# h.net
KiCad netlist of a schematic drawn in EAGLE
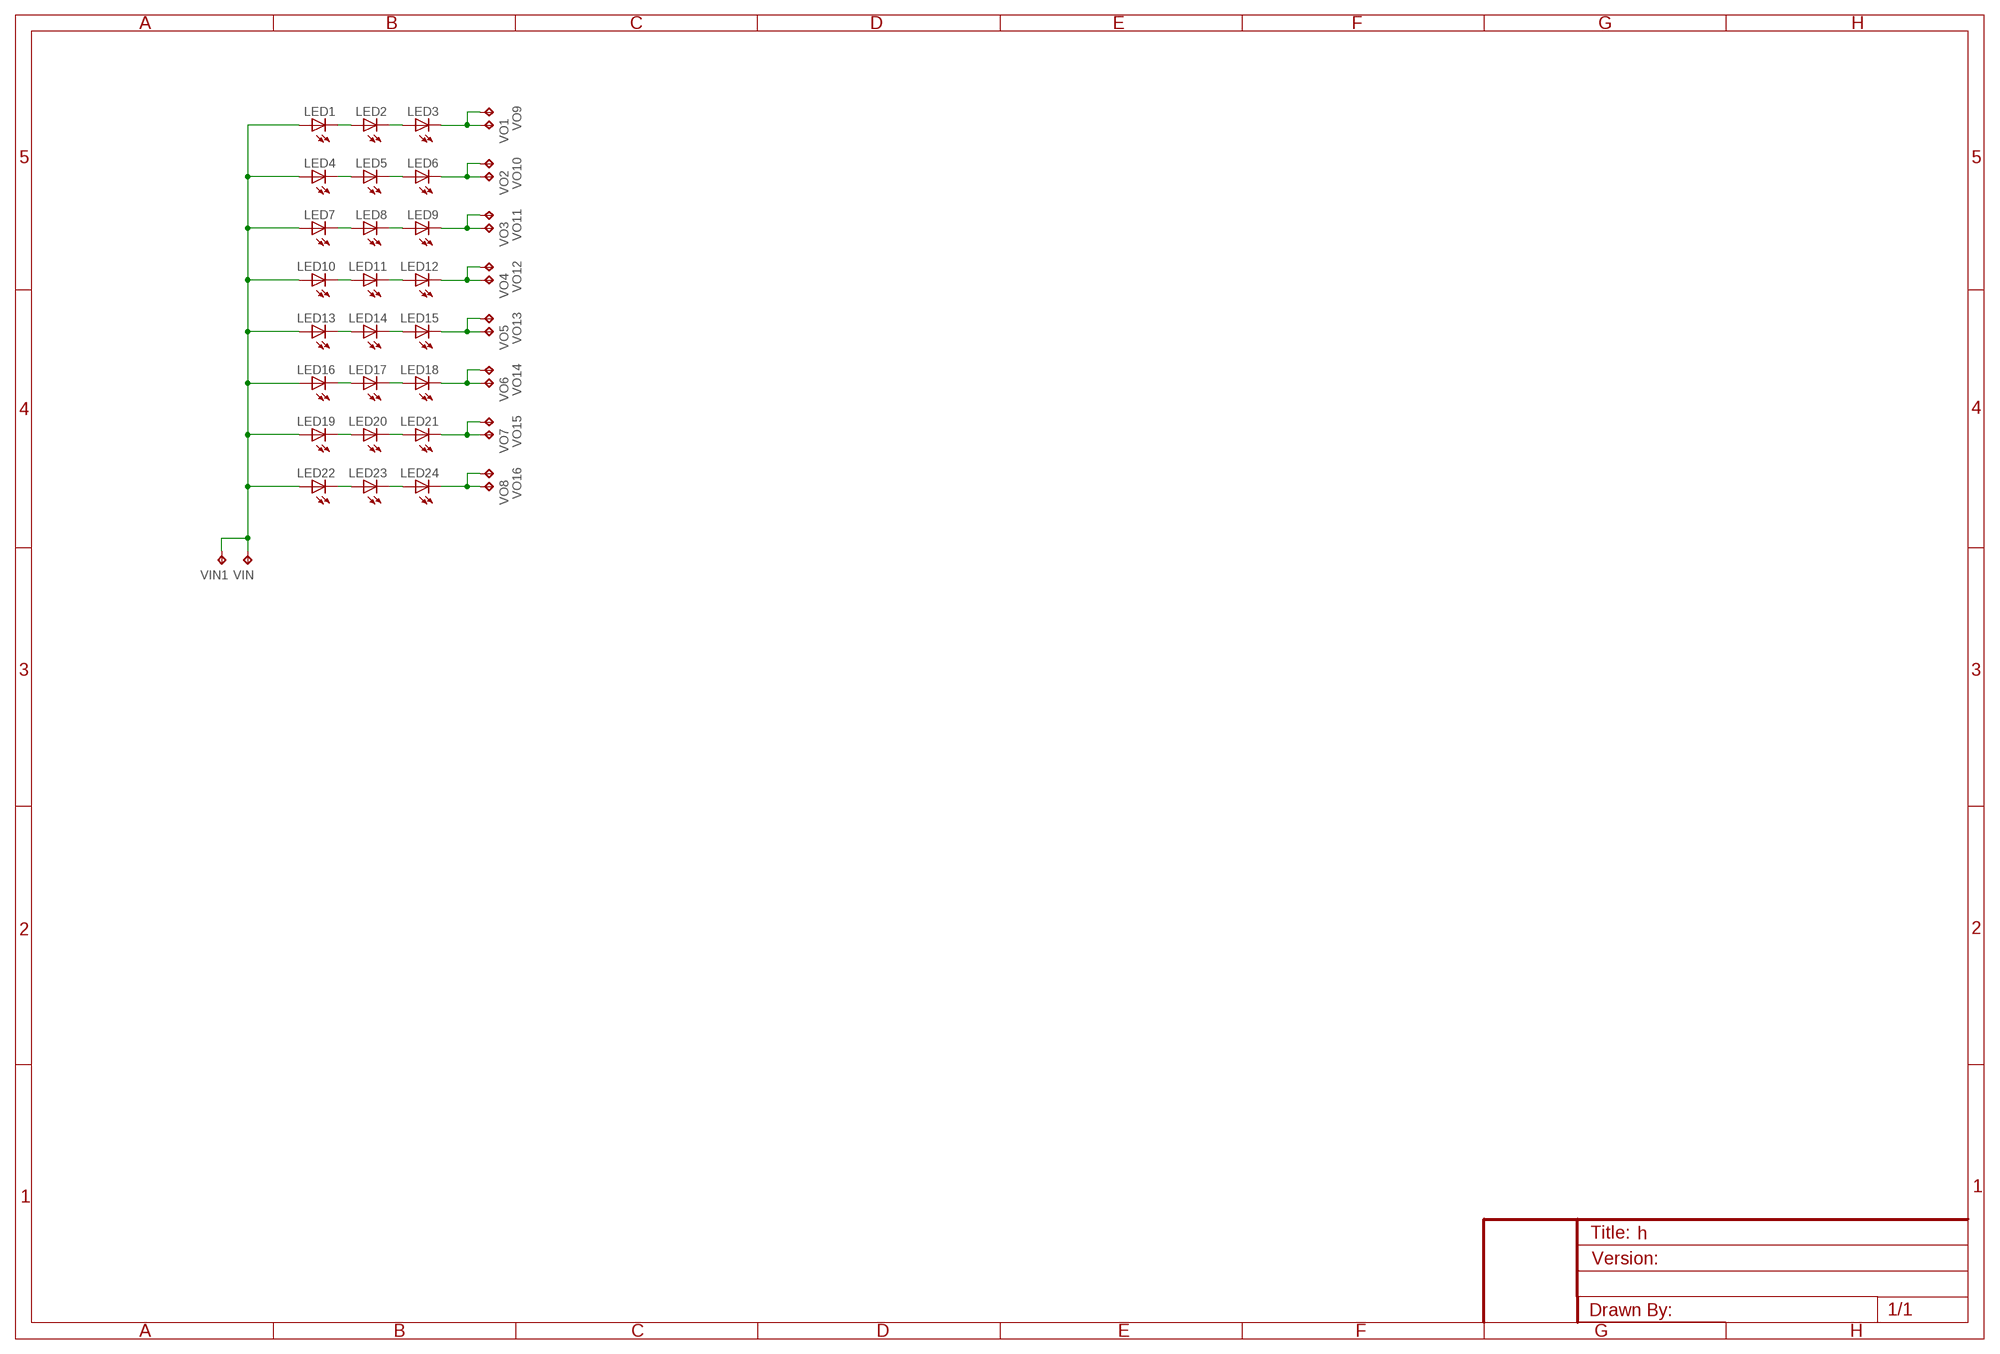
[diagram p0: schematic, sheet 1]

(export (version "E")
  (design (tool "Eeschema 10.0.6"))
  (components
    (comp (ref "LED1")
      (value "LED0805")
      (footprint "eagle-import:LED_0805")
      (libsource (lib "eagle-import") (part "LED0805"))
    )
    (comp (ref "LED2")
      (value "LED0805")
      (footprint "eagle-import:LED_0805")
      (libsource (lib "eagle-import") (part "LED0805"))
    )
    (comp (ref "LED3")
      (value "LED0805")
      (footprint "eagle-import:LED_0805")
      (libsource (lib "eagle-import") (part "LED0805"))
    )
    (comp (ref "LED4")
      (value "LED0805")
      (footprint "eagle-import:LED_0805")
      (libsource (lib "eagle-import") (part "LED0805"))
    )
    (comp (ref "LED5")
      (value "LED0805")
      (footprint "eagle-import:LED_0805")
      (libsource (lib "eagle-import") (part "LED0805"))
    )
    (comp (ref "LED6")
      (value "LED0805")
      (footprint "eagle-import:LED_0805")
      (libsource (lib "eagle-import") (part "LED0805"))
    )
    (comp (ref "LED7")
      (value "LED0805")
      (footprint "eagle-import:LED_0805")
      (libsource (lib "eagle-import") (part "LED0805"))
    )
    (comp (ref "LED8")
      (value "LED0805")
      (footprint "eagle-import:LED_0805")
      (libsource (lib "eagle-import") (part "LED0805"))
    )
    (comp (ref "LED9")
      (value "LED0805")
      (footprint "eagle-import:LED_0805")
      (libsource (lib "eagle-import") (part "LED0805"))
    )
    (comp (ref "LED10")
      (value "LED0805")
      (footprint "eagle-import:LED_0805")
      (libsource (lib "eagle-import") (part "LED0805"))
    )
    (comp (ref "LED11")
      (value "LED0805")
      (footprint "eagle-import:LED_0805")
      (libsource (lib "eagle-import") (part "LED0805"))
    )
    (comp (ref "LED12")
      (value "LED0805")
      (footprint "eagle-import:LED_0805")
      (libsource (lib "eagle-import") (part "LED0805"))
    )
    (comp (ref "LED13")
      (value "LED0805")
      (footprint "eagle-import:LED_0805")
      (libsource (lib "eagle-import") (part "LED0805"))
    )
    (comp (ref "LED14")
      (value "LED0805")
      (footprint "eagle-import:LED_0805")
      (libsource (lib "eagle-import") (part "LED0805"))
    )
    (comp (ref "LED15")
      (value "LED0805")
      (footprint "eagle-import:LED_0805")
      (libsource (lib "eagle-import") (part "LED0805"))
    )
    (comp (ref "LED16")
      (value "LED0805")
      (footprint "eagle-import:LED_0805")
      (libsource (lib "eagle-import") (part "LED0805"))
    )
    (comp (ref "LED17")
      (value "LED0805")
      (footprint "eagle-import:LED_0805")
      (libsource (lib "eagle-import") (part "LED0805"))
    )
    (comp (ref "LED18")
      (value "LED0805")
      (footprint "eagle-import:LED_0805")
      (libsource (lib "eagle-import") (part "LED0805"))
    )
    (comp (ref "LED19")
      (value "LED0805")
      (footprint "eagle-import:LED_0805")
      (libsource (lib "eagle-import") (part "LED0805"))
    )
    (comp (ref "LED20")
      (value "LED0805")
      (footprint "eagle-import:LED_0805")
      (libsource (lib "eagle-import") (part "LED0805"))
    )
    (comp (ref "LED21")
      (value "LED0805")
      (footprint "eagle-import:LED_0805")
      (libsource (lib "eagle-import") (part "LED0805"))
    )
    (comp (ref "LED22")
      (value "LED0805")
      (footprint "eagle-import:LED_0805")
      (libsource (lib "eagle-import") (part "LED0805"))
    )
    (comp (ref "LED23")
      (value "LED0805")
      (footprint "eagle-import:LED_0805")
      (libsource (lib "eagle-import") (part "LED0805"))
    )
    (comp (ref "LED24")
      (value "LED0805")
      (footprint "eagle-import:LED_0805")
      (libsource (lib "eagle-import") (part "LED0805"))
    )
    (comp (ref "VIN")
      (value "TEST_POINTPAD1-20")
      (footprint "eagle-import:P1-20")
      (libsource (lib "eagle-import") (part "TEST_POINTPAD1-20"))
    )
    (comp (ref "VIN1")
      (value "TEST_POINTPAD1-20")
      (footprint "eagle-import:P1-20")
      (libsource (lib "eagle-import") (part "TEST_POINTPAD1-20"))
    )
    (comp (ref "VO1")
      (value "TEST_POINTPAD1-20")
      (footprint "eagle-import:P1-20")
      (libsource (lib "eagle-import") (part "TEST_POINTPAD1-20"))
    )
    (comp (ref "VO2")
      (value "TEST_POINTPAD1-20")
      (footprint "eagle-import:P1-20")
      (libsource (lib "eagle-import") (part "TEST_POINTPAD1-20"))
    )
    (comp (ref "VO3")
      (value "TEST_POINTPAD1-20")
      (footprint "eagle-import:P1-20")
      (libsource (lib "eagle-import") (part "TEST_POINTPAD1-20"))
    )
    (comp (ref "VO4")
      (value "TEST_POINTPAD1-20")
      (footprint "eagle-import:P1-20")
      (libsource (lib "eagle-import") (part "TEST_POINTPAD1-20"))
    )
    (comp (ref "VO5")
      (value "TEST_POINTPAD1-20")
      (footprint "eagle-import:P1-20")
      (libsource (lib "eagle-import") (part "TEST_POINTPAD1-20"))
    )
    (comp (ref "VO6")
      (value "TEST_POINTPAD1-20")
      (footprint "eagle-import:P1-20")
      (libsource (lib "eagle-import") (part "TEST_POINTPAD1-20"))
    )
    (comp (ref "VO7")
      (value "TEST_POINTPAD1-20")
      (footprint "eagle-import:P1-20")
      (libsource (lib "eagle-import") (part "TEST_POINTPAD1-20"))
    )
    (comp (ref "VO8")
      (value "TEST_POINTPAD1-20")
      (footprint "eagle-import:P1-20")
      (libsource (lib "eagle-import") (part "TEST_POINTPAD1-20"))
    )
    (comp (ref "VO9")
      (value "TEST_POINTPAD1-20")
      (footprint "eagle-import:P1-20")
      (libsource (lib "eagle-import") (part "TEST_POINTPAD1-20"))
    )
    (comp (ref "VO10")
      (value "TEST_POINTPAD1-20")
      (footprint "eagle-import:P1-20")
      (libsource (lib "eagle-import") (part "TEST_POINTPAD1-20"))
    )
    (comp (ref "VO11")
      (value "TEST_POINTPAD1-20")
      (footprint "eagle-import:P1-20")
      (libsource (lib "eagle-import") (part "TEST_POINTPAD1-20"))
    )
    (comp (ref "VO12")
      (value "TEST_POINTPAD1-20")
      (footprint "eagle-import:P1-20")
      (libsource (lib "eagle-import") (part "TEST_POINTPAD1-20"))
    )
    (comp (ref "VO13")
      (value "TEST_POINTPAD1-20")
      (footprint "eagle-import:P1-20")
      (libsource (lib "eagle-import") (part "TEST_POINTPAD1-20"))
    )
    (comp (ref "VO14")
      (value "TEST_POINTPAD1-20")
      (footprint "eagle-import:P1-20")
      (libsource (lib "eagle-import") (part "TEST_POINTPAD1-20"))
    )
    (comp (ref "VO15")
      (value "TEST_POINTPAD1-20")
      (footprint "eagle-import:P1-20")
      (libsource (lib "eagle-import") (part "TEST_POINTPAD1-20"))
    )
    (comp (ref "VO16")
      (value "TEST_POINTPAD1-20")
      (footprint "eagle-import:P1-20")
      (libsource (lib "eagle-import") (part "TEST_POINTPAD1-20"))
    )
  )
  (nets
    (net (code "1") (name "Net-(LED1-PadA)") (class "Default")
      (node (ref "LED1") (pin "A") (pinfunction "A_A") (pintype "passive"))
      (node (ref "LED10") (pin "A") (pinfunction "A_A") (pintype "passive"))
      (node (ref "LED13") (pin "A") (pinfunction "A_A") (pintype "passive"))
      (node (ref "LED16") (pin "A") (pinfunction "A_A") (pintype "passive"))
      (node (ref "LED19") (pin "A") (pinfunction "A_A") (pintype "passive"))
      (node (ref "LED22") (pin "A") (pinfunction "A_A") (pintype "passive"))
      (node (ref "LED4") (pin "A") (pinfunction "A_A") (pintype "passive"))
      (node (ref "LED7") (pin "A") (pinfunction "A_A") (pintype "passive"))
      (node (ref "VIN") (pin "TP") (pinfunction "TP_TP") (pintype "input"))
      (node (ref "VIN1") (pin "TP") (pinfunction "TP_TP") (pintype "input"))
    )
    (net (code "2") (name "Net-(LED1-PadC)") (class "Default")
      (node (ref "LED1") (pin "C") (pinfunction "C_C") (pintype "passive"))
      (node (ref "LED2") (pin "A") (pinfunction "A_A") (pintype "passive"))
    )
    (net (code "3") (name "Net-(LED2-PadC)") (class "Default")
      (node (ref "LED2") (pin "C") (pinfunction "C_C") (pintype "passive"))
      (node (ref "LED3") (pin "A") (pinfunction "A_A") (pintype "passive"))
    )
    (net (code "4") (name "Net-(LED3-PadC)") (class "Default")
      (node (ref "LED3") (pin "C") (pinfunction "C_C") (pintype "passive"))
      (node (ref "VO1") (pin "TP") (pinfunction "TP_TP") (pintype "input"))
      (node (ref "VO9") (pin "TP") (pinfunction "TP_TP") (pintype "input"))
    )
    (net (code "5") (name "Net-(LED4-PadC)") (class "Default")
      (node (ref "LED4") (pin "C") (pinfunction "C_C") (pintype "passive"))
      (node (ref "LED5") (pin "A") (pinfunction "A_A") (pintype "passive"))
    )
    (net (code "6") (name "Net-(LED5-PadC)") (class "Default")
      (node (ref "LED5") (pin "C") (pinfunction "C_C") (pintype "passive"))
      (node (ref "LED6") (pin "A") (pinfunction "A_A") (pintype "passive"))
    )
    (net (code "7") (name "Net-(LED6-PadC)") (class "Default")
      (node (ref "LED6") (pin "C") (pinfunction "C_C") (pintype "passive"))
      (node (ref "VO10") (pin "TP") (pinfunction "TP_TP") (pintype "input"))
      (node (ref "VO2") (pin "TP") (pinfunction "TP_TP") (pintype "input"))
    )
    (net (code "8") (name "Net-(LED7-PadC)") (class "Default")
      (node (ref "LED7") (pin "C") (pinfunction "C_C") (pintype "passive"))
      (node (ref "LED8") (pin "A") (pinfunction "A_A") (pintype "passive"))
    )
    (net (code "9") (name "Net-(LED8-PadC)") (class "Default")
      (node (ref "LED8") (pin "C") (pinfunction "C_C") (pintype "passive"))
      (node (ref "LED9") (pin "A") (pinfunction "A_A") (pintype "passive"))
    )
    (net (code "10") (name "Net-(LED9-PadC)") (class "Default")
      (node (ref "LED9") (pin "C") (pinfunction "C_C") (pintype "passive"))
      (node (ref "VO11") (pin "TP") (pinfunction "TP_TP") (pintype "input"))
      (node (ref "VO3") (pin "TP") (pinfunction "TP_TP") (pintype "input"))
    )
    (net (code "11") (name "Net-(LED10-PadC)") (class "Default")
      (node (ref "LED10") (pin "C") (pinfunction "C_C") (pintype "passive"))
      (node (ref "LED11") (pin "A") (pinfunction "A_A") (pintype "passive"))
    )
    (net (code "12") (name "Net-(LED11-PadC)") (class "Default")
      (node (ref "LED11") (pin "C") (pinfunction "C_C") (pintype "passive"))
      (node (ref "LED12") (pin "A") (pinfunction "A_A") (pintype "passive"))
    )
    (net (code "13") (name "Net-(LED12-PadC)") (class "Default")
      (node (ref "LED12") (pin "C") (pinfunction "C_C") (pintype "passive"))
      (node (ref "VO12") (pin "TP") (pinfunction "TP_TP") (pintype "input"))
      (node (ref "VO4") (pin "TP") (pinfunction "TP_TP") (pintype "input"))
    )
    (net (code "14") (name "Net-(LED13-PadC)") (class "Default")
      (node (ref "LED13") (pin "C") (pinfunction "C_C") (pintype "passive"))
      (node (ref "LED14") (pin "A") (pinfunction "A_A") (pintype "passive"))
    )
    (net (code "15") (name "Net-(LED14-PadC)") (class "Default")
      (node (ref "LED14") (pin "C") (pinfunction "C_C") (pintype "passive"))
      (node (ref "LED15") (pin "A") (pinfunction "A_A") (pintype "passive"))
    )
    (net (code "16") (name "Net-(LED15-PadC)") (class "Default")
      (node (ref "LED15") (pin "C") (pinfunction "C_C") (pintype "passive"))
      (node (ref "VO13") (pin "TP") (pinfunction "TP_TP") (pintype "input"))
      (node (ref "VO5") (pin "TP") (pinfunction "TP_TP") (pintype "input"))
    )
    (net (code "17") (name "Net-(LED16-PadC)") (class "Default")
      (node (ref "LED16") (pin "C") (pinfunction "C_C") (pintype "passive"))
      (node (ref "LED17") (pin "A") (pinfunction "A_A") (pintype "passive"))
    )
    (net (code "18") (name "Net-(LED17-PadC)") (class "Default")
      (node (ref "LED17") (pin "C") (pinfunction "C_C") (pintype "passive"))
      (node (ref "LED18") (pin "A") (pinfunction "A_A") (pintype "passive"))
    )
    (net (code "19") (name "Net-(LED18-PadC)") (class "Default")
      (node (ref "LED18") (pin "C") (pinfunction "C_C") (pintype "passive"))
      (node (ref "VO14") (pin "TP") (pinfunction "TP_TP") (pintype "input"))
      (node (ref "VO6") (pin "TP") (pinfunction "TP_TP") (pintype "input"))
    )
    (net (code "20") (name "Net-(LED19-PadC)") (class "Default")
      (node (ref "LED19") (pin "C") (pinfunction "C_C") (pintype "passive"))
      (node (ref "LED20") (pin "A") (pinfunction "A_A") (pintype "passive"))
    )
    (net (code "21") (name "Net-(LED20-PadC)") (class "Default")
      (node (ref "LED20") (pin "C") (pinfunction "C_C") (pintype "passive"))
      (node (ref "LED21") (pin "A") (pinfunction "A_A") (pintype "passive"))
    )
    (net (code "22") (name "Net-(LED21-PadC)") (class "Default")
      (node (ref "LED21") (pin "C") (pinfunction "C_C") (pintype "passive"))
      (node (ref "VO15") (pin "TP") (pinfunction "TP_TP") (pintype "input"))
      (node (ref "VO7") (pin "TP") (pinfunction "TP_TP") (pintype "input"))
    )
    (net (code "23") (name "Net-(LED22-PadC)") (class "Default")
      (node (ref "LED22") (pin "C") (pinfunction "C_C") (pintype "passive"))
      (node (ref "LED23") (pin "A") (pinfunction "A_A") (pintype "passive"))
    )
    (net (code "24") (name "Net-(LED23-PadC)") (class "Default")
      (node (ref "LED23") (pin "C") (pinfunction "C_C") (pintype "passive"))
      (node (ref "LED24") (pin "A") (pinfunction "A_A") (pintype "passive"))
    )
    (net (code "25") (name "Net-(LED24-PadC)") (class "Default")
      (node (ref "LED24") (pin "C") (pinfunction "C_C") (pintype "passive"))
      (node (ref "VO16") (pin "TP") (pinfunction "TP_TP") (pintype "input"))
      (node (ref "VO8") (pin "TP") (pinfunction "TP_TP") (pintype "input"))
    )
  )
)
